# Battery_Monitor.net
KiCad netlist of a schematic drawn in Altium Designer
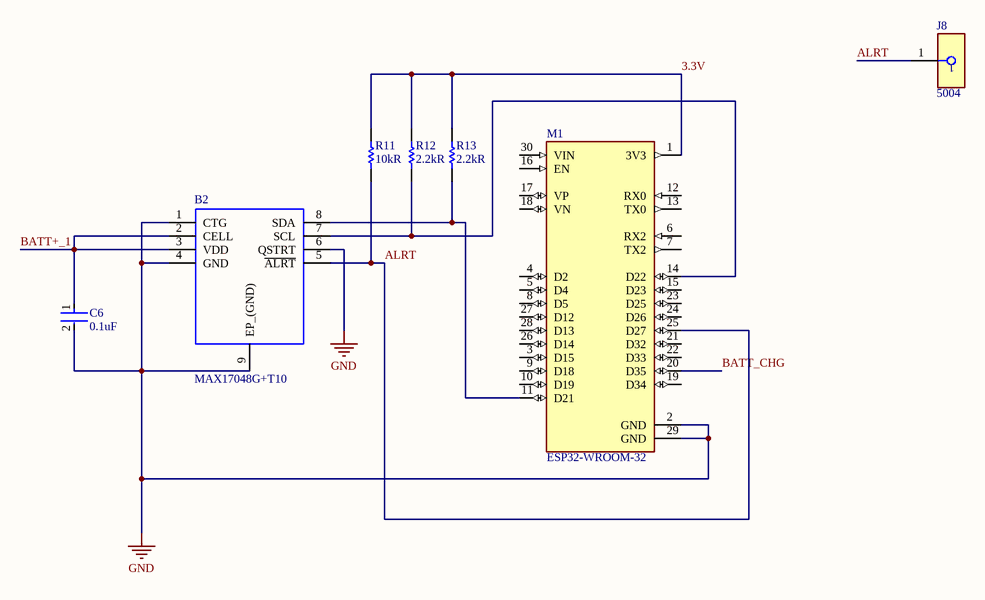
[diagram p0: Battery_Monitor.SchDoc]

(export (version "E")
  (design (tool "Eeschema 10.0.6"))
  (components
    (comp (ref "B2")
      (value "MAX17048G+T10")
      (footprint "SON50P200X200X80-9N-D")
      (description "Battery Management Host-Side Modelgauge (1-Cell)")
      (fields
        (field (name "MANUFACTURER") "Maxim Integrated")
        (field (name "MOUSER PART NUMBER") "700-MAX17048G+T10")
      )
      (libsource (lib "MAX17048G+T10") (part "MAX17048G+T10"))
    )
    (comp (ref "C6")
      (value "0.1uF")
      (footprint "FP-CC0402-MFG")
      (description "CAP CER 0.1UF 16V X5R 0402")
      (fields
        (field (name "MFR. PART #") "CC0402KRX5R7BB104")
        (field (name "OCTOPART") "https://octopart.com/cc0402krx5r7bb104-yageo-8376508")
      )
      (libsource (lib "Altium Content Vault") (part "11868f565c42a9108669ba33697ecf6"))
    )
    (comp (ref "J8")
      (value "5004")
      (footprint "FP-5004-MFG")
      (description "PC TEST POINT MINIATURE YELLOW")
      (fields
        (field (name "MANUFACTURER") "Keystone")
        (field (name "OCTOPART") "https://octopart.com/5004-keystone-28591")
      )
      (libsource (lib "Altium Content Vault") (part "98815daf2f2c152b0c43f5ab9800df6"))
    )
    (comp (ref "M1")
      (value "ESP32-WROOM-32")
      (footprint "ESP32-DEVKIT-V1")
      (libsource (lib "Modules") (part "ESP32-DEVKIT-V1"))
    )
    (comp (ref "R11")
      (value "10kR")
      (footprint "RESC1005X40X25LL05T10")
      (fields
        (field (name "MFR. PART #") "RC0402FR-0710KL")
        (field (name "MANUFACTURER") "Yageo / Phycomp")
        (field (name "LCSC PART #") "C60490")
      )
      (libsource (lib "Altium Content Vault") (part "RES"))
    )
    (comp (ref "R12")
      (value "2.2kR")
      (footprint "RESC1005X40X25ML05T10")
      (fields
        (field (name "MANUFACTURER") "Yageo / Phycomp")
        (field (name "MFR. PART #") "RC0402FR-072K2L")
        (field (name "LCSC PART #") "C114762")
      )
      (libsource (lib "Altium Content Vault") (part "RES"))
    )
    (comp (ref "R13")
      (value "2.2kR")
      (footprint "RESC1005X40X25ML05T10")
      (fields
        (field (name "MANUFACTURER") "Yageo / Phycomp")
        (field (name "MFR. PART #") "RC0402FR-072K2L")
        (field (name "LCSC PART #") "C114762")
      )
      (libsource (lib "Altium Content Vault") (part "RES"))
    )
  )
  (nets
    (net (code "1") (name "/3.3V") (class "Default")
      (node (ref "M1") (pin "1") (pinfunction "3V3_1") (pintype "output"))
      (node (ref "R11") (pin "2") (pinfunction "2_2") (pintype "passive"))
      (node (ref "R12") (pin "2") (pinfunction "2_2") (pintype "passive"))
      (node (ref "R13") (pin "2") (pinfunction "2_2") (pintype "passive"))
    )
    (net (code "2") (name "/ALRT") (class "Default")
      (node (ref "B2") (pin "5") (pinfunction "ALRT_5") (pintype "passive"))
      (node (ref "J8") (pin "1") (pinfunction "1_1") (pintype "passive"))
      (node (ref "M1") (pin "25") (pinfunction "D27_25") (pintype "bidirectional"))
      (node (ref "R11") (pin "1") (pinfunction "1_1") (pintype "passive"))
    )
    (net (code "3") (name "/BATT+_1") (class "Default")
      (node (ref "B2") (pin "2") (pinfunction "CELL_2") (pintype "passive"))
      (node (ref "B2") (pin "3") (pinfunction "VDD_3") (pintype "passive"))
      (node (ref "C6") (pin "1") (pinfunction "1_1") (pintype "passive"))
    )
    (net (code "4") (name "/BATT_CHG") (class "Default")
      (node (ref "M1") (pin "20") (pinfunction "D35_20") (pintype "bidirectional"))
    )
    (net (code "5") (name "GND") (class "Default")
      (node (ref "B2") (pin "1") (pinfunction "CTG_1") (pintype "passive"))
      (node (ref "B2") (pin "4") (pinfunction "GND_4") (pintype "passive"))
      (node (ref "B2") (pin "6") (pinfunction "QSTRT_6") (pintype "passive"))
      (node (ref "B2") (pin "9") (pinfunction "EP_(GND)_9") (pintype "passive"))
      (node (ref "C6") (pin "2") (pinfunction "2_2") (pintype "passive"))
      (node (ref "M1") (pin "2") (pinfunction "GND_2") (pintype "power_in"))
      (node (ref "M1") (pin "29") (pinfunction "GND_29") (pintype "power_in"))
    )
    (net (code "6") (name "Net-(B2-SCL)") (class "Default")
      (node (ref "B2") (pin "7") (pinfunction "SCL_7") (pintype "passive"))
      (node (ref "M1") (pin "14") (pinfunction "D22_14") (pintype "bidirectional"))
      (node (ref "R12") (pin "1") (pinfunction "1_1") (pintype "passive"))
    )
    (net (code "7") (name "Net-(B2-SDA)") (class "Default")
      (node (ref "B2") (pin "8") (pinfunction "SDA_8") (pintype "passive"))
      (node (ref "M1") (pin "11") (pinfunction "D21_11") (pintype "bidirectional"))
      (node (ref "R13") (pin "1") (pinfunction "1_1") (pintype "passive"))
    )
    (net (code "8") (name "unconnected-(M1-D2-Pad4)") (class "Default")
      (node (ref "M1") (pin "4") (pinfunction "D2_4") (pintype "bidirectional"))
    )
    (net (code "9") (name "unconnected-(M1-D4-Pad5)") (class "Default")
      (node (ref "M1") (pin "5") (pinfunction "D4_5") (pintype "bidirectional"))
    )
    (net (code "10") (name "unconnected-(M1-D5-Pad8)") (class "Default")
      (node (ref "M1") (pin "8") (pinfunction "D5_8") (pintype "bidirectional"))
    )
    (net (code "11") (name "unconnected-(M1-D12-Pad27)") (class "Default")
      (node (ref "M1") (pin "27") (pinfunction "D12_27") (pintype "bidirectional"))
    )
    (net (code "12") (name "unconnected-(M1-D13-Pad28)") (class "Default")
      (node (ref "M1") (pin "28") (pinfunction "D13_28") (pintype "bidirectional"))
    )
    (net (code "13") (name "unconnected-(M1-D14-Pad26)") (class "Default")
      (node (ref "M1") (pin "26") (pinfunction "D14_26") (pintype "bidirectional"))
    )
    (net (code "14") (name "unconnected-(M1-D15-Pad3)") (class "Default")
      (node (ref "M1") (pin "3") (pinfunction "D15_3") (pintype "bidirectional"))
    )
    (net (code "15") (name "unconnected-(M1-D18-Pad9)") (class "Default")
      (node (ref "M1") (pin "9") (pinfunction "D18_9") (pintype "bidirectional"))
    )
    (net (code "16") (name "unconnected-(M1-D19-Pad10)") (class "Default")
      (node (ref "M1") (pin "10") (pinfunction "D19_10") (pintype "bidirectional"))
    )
    (net (code "17") (name "unconnected-(M1-D23-Pad15)") (class "Default")
      (node (ref "M1") (pin "15") (pinfunction "D23_15") (pintype "bidirectional"))
    )
    (net (code "18") (name "unconnected-(M1-D25-Pad23)") (class "Default")
      (node (ref "M1") (pin "23") (pinfunction "D25_23") (pintype "bidirectional"))
    )
    (net (code "19") (name "unconnected-(M1-D26-Pad24)") (class "Default")
      (node (ref "M1") (pin "24") (pinfunction "D26_24") (pintype "bidirectional"))
    )
    (net (code "20") (name "unconnected-(M1-D32-Pad21)") (class "Default")
      (node (ref "M1") (pin "21") (pinfunction "D32_21") (pintype "bidirectional"))
    )
    (net (code "21") (name "unconnected-(M1-D33-Pad22)") (class "Default")
      (node (ref "M1") (pin "22") (pinfunction "D33_22") (pintype "bidirectional"))
    )
    (net (code "22") (name "unconnected-(M1-D34-Pad19)") (class "Default")
      (node (ref "M1") (pin "19") (pinfunction "D34_19") (pintype "bidirectional"))
    )
    (net (code "23") (name "unconnected-(M1-EN-Pad16)") (class "Default")
      (node (ref "M1") (pin "16") (pinfunction "EN_16") (pintype "input"))
    )
    (net (code "24") (name "unconnected-(M1-RX0-Pad12)") (class "Default")
      (node (ref "M1") (pin "12") (pinfunction "RX0_12") (pintype "input"))
    )
    (net (code "25") (name "unconnected-(M1-RX2-Pad6)") (class "Default")
      (node (ref "M1") (pin "6") (pinfunction "RX2_6") (pintype "input"))
    )
    (net (code "26") (name "unconnected-(M1-TX0-Pad13)") (class "Default")
      (node (ref "M1") (pin "13") (pinfunction "TX0_13") (pintype "output"))
    )
    (net (code "27") (name "unconnected-(M1-TX2-Pad7)") (class "Default")
      (node (ref "M1") (pin "7") (pinfunction "TX2_7") (pintype "output"))
    )
    (net (code "28") (name "unconnected-(M1-VIN-Pad30)") (class "Default")
      (node (ref "M1") (pin "30") (pinfunction "VIN_30") (pintype "input"))
    )
    (net (code "29") (name "unconnected-(M1-VN-Pad18)") (class "Default")
      (node (ref "M1") (pin "18") (pinfunction "VN_18") (pintype "bidirectional"))
    )
    (net (code "30") (name "unconnected-(M1-VP-Pad17)") (class "Default")
      (node (ref "M1") (pin "17") (pinfunction "VP_17") (pintype "bidirectional"))
    )
  )
)
